# H2AR1_Backend.net
KiCad netlist of a schematic drawn in Altium Designer
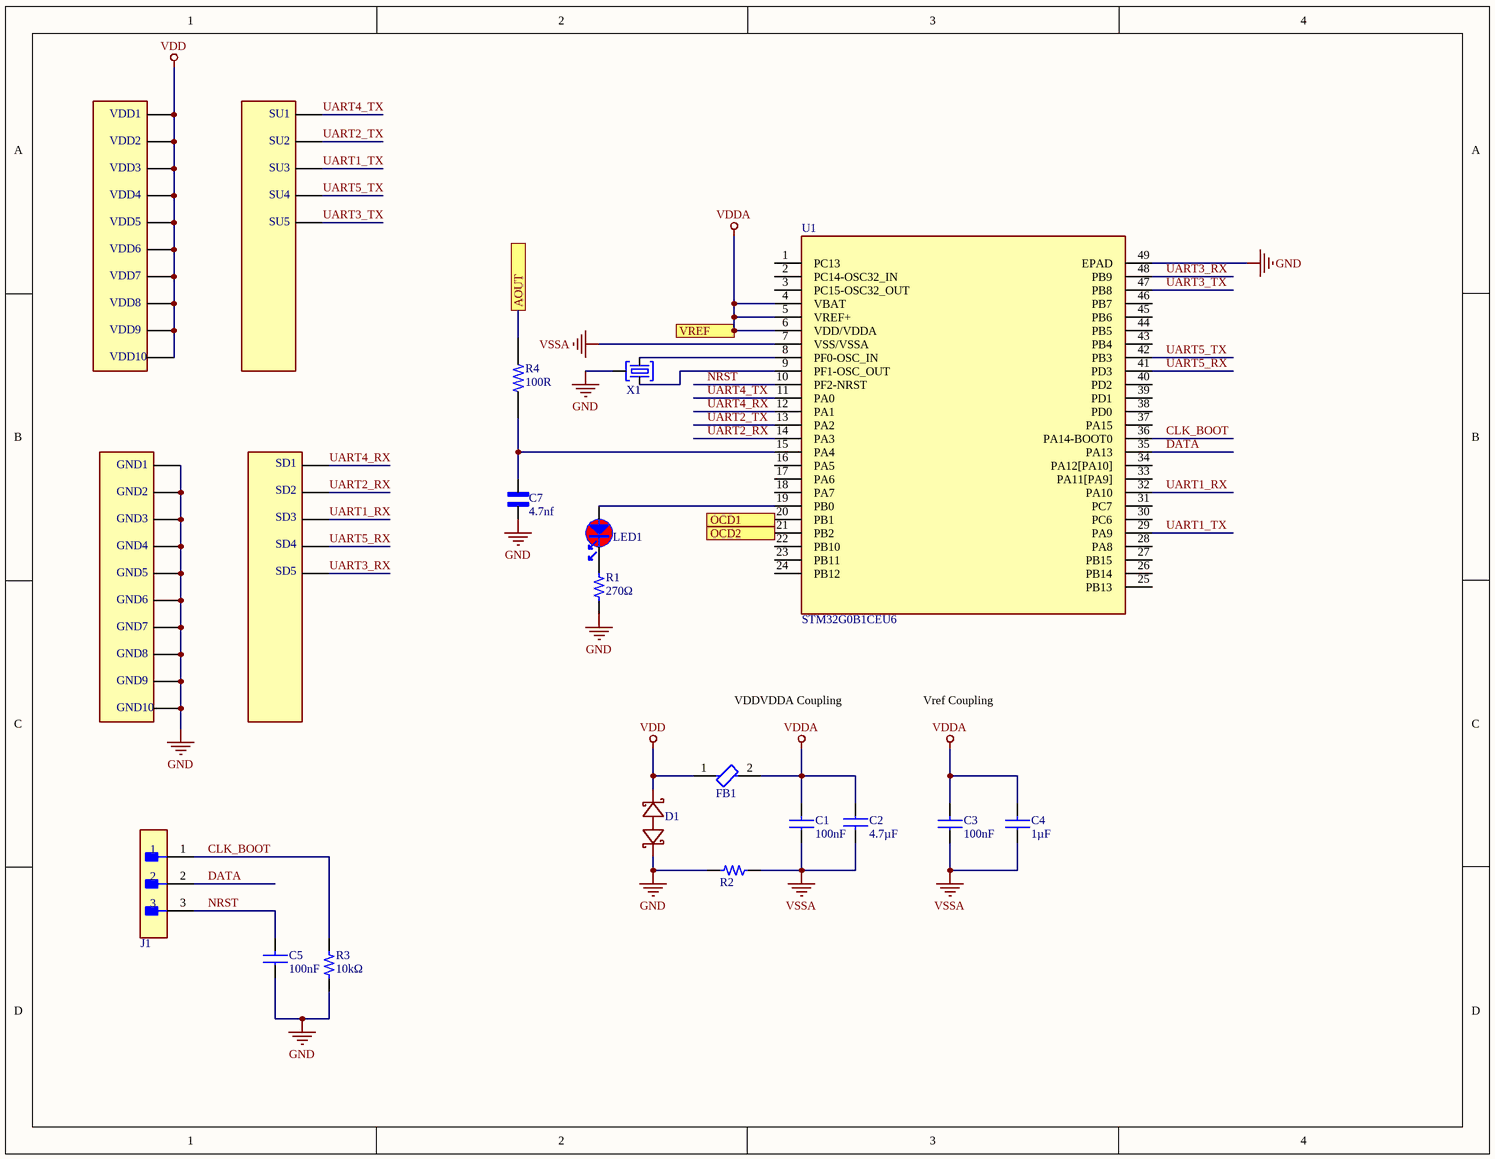
[diagram p0: H2AR1_Backend.SchDoc]

(export (version "E")
  (design (tool "Eeschema 10.0.6"))
  (components
    (comp (ref "C1")
      (value "100nF")
      (footprint "C0603")
      (fields
        (field (name "MANUFACTURER") "Samsung Electro-Mechanics")
        (field (name "MANUFACTURER PART NUMBER") "CL10B104KA8NNNC")
        (field (name "TOLERANCE") "10%")
      )
      (libsource (lib "Hexabitz Altium Library") (part "generic Capacitor"))
    )
    (comp (ref "C2")
      (value "4.7µF")
      (footprint "C0805")
      (fields
        (field (name "MANUFACTURER") "Samsung Electro-Mechanics")
        (field (name "MANUFACTURER PART NUMBER") "CL21X475KAQNNNE")
        (field (name "TOLERANCE") "10%")
      )
      (libsource (lib "Hexabitz Altium Library") (part "generic Capacitor"))
    )
    (comp (ref "C3")
      (value "100nF")
      (footprint "C0603")
      (fields
        (field (name "MANUFACTURER") "Samsung Electro-Mechanics")
        (field (name "MANUFACTURER PART NUMBER") "CL10B104KA8NNNC")
        (field (name "TOLERANCE") "10%")
      )
      (libsource (lib "Hexabitz Altium Library") (part "generic Capacitor"))
    )
    (comp (ref "C4")
      (value "1µF")
      (footprint "C0805")
      (description "Ceramic Capacitor, Ceramic, 16V, 10% +Tol, 10% -Tol, X7R, 15% TC, 1uF, Surface Mount, 0805")
      (fields
        (field (name "MANUFACTURER") "Yageo Group")
        (field (name "MANUFACTURER PART NUMBER") "CC0805KKX7R7BB105")
      )
      (libsource (lib "Hexabitz Altium Library") (part "generic Capacitor"))
    )
    (comp (ref "C5")
      (value "100nF")
      (footprint "C0603")
      (fields
        (field (name "MANUFACTURER") "Samsung Electro-Mechanics")
        (field (name "MANUFACTURER PART NUMBER") "CL10B104KA8NNNC")
        (field (name "TOLERANCE") "10%")
      )
      (libsource (lib "Hexabitz Altium Library") (part "generic Capacitor"))
    )
    (comp (ref "C7")
      (value "4.7nf")
      (footprint "CAPC0603X33N")
      (description "SMD Capacitor C0G(EIA) with Capacitance: 0.60pF Tol. 0.1pF. Rated Voltage: 50Vdc")
      (fields (field (name "MF") "Murata") (field (name "MP") "GRM0335C1HR60BA01D"))
      (libsource (lib "GRM0335C1HR60BA01D") (part "GRM0335C1HR60BA01D"))
    )
    (comp (ref "D1")
      (value "CDSOD323-T03SC")
      (footprint "SOD2513X114N")
      (description "A 3V, 350W, bi-directional, standard capacitance, SOD323 pkg TVS Diode ¦ Bourns CDSOD323-T03SC")
      (fields (field (name "MANUFACTURER") "Bourns"))
      (libsource (lib "Hexabitz Altium Library") (part "CDSOD323-T03SC"))
    )
    (comp (ref "FB1")
      (value "MMZ1608Y300B")
      (footprint "FP-MMZ1608-0_8-MFG")
      (description "Ferrite Beads 0603 30ohms 1500mA Signal Line AEC-Q200")
      (fields
        (field (name "MANUFACTURER") "TDK")
        (field (name "MANUFACTURER PART NUMBER") "MMZ1608Y300BTD25")
      )
      (libsource (lib "Hexabitz Altium Library") (part "MMZ1608Y300B"))
    )
    (comp (ref "GND1")
      (value "HEXABIT_UART_PORT")
      (footprint "HEXABIT_POWER_PORT_D")
      (libsource (lib "hexabitz_connectors.Library") (part "HEXABIT_POWER_PORT_D"))
    )
    (comp (ref "GND2")
      (value "HEXABIT_UART_PORT")
      (footprint "HEXABIT_POWER_PORT_D")
      (libsource (lib "hexabitz_connectors.Library") (part "HEXABIT_POWER_PORT_D"))
    )
    (comp (ref "GND3")
      (value "HEXABIT_UART_PORT")
      (footprint "HEXABIT_POWER_PORT_D_300R")
      (libsource (lib "hexabitz_connectors.Library") (part "HEXABIT_POWER_PORT_D_300R"))
    )
    (comp (ref "GND4")
      (value "HEXABIT_UART_PORT")
      (footprint "HEXABIT_POWER_PORT_D")
      (libsource (lib "hexabitz_connectors.Library") (part "HEXABIT_POWER_PORT_D"))
    )
    (comp (ref "GND5")
      (value "HEXABIT_UART_PORT")
      (footprint "HEXABIT_POWER_PORT_D")
      (libsource (lib "hexabitz_connectors.Library") (part "HEXABIT_POWER_PORT_D"))
    )
    (comp (ref "GND6")
      (value "HEXABIT_UART_PORT")
      (footprint "HEXABIT_POWER_PORT_D")
      (libsource (lib "hexabitz_connectors.Library") (part "HEXABIT_POWER_PORT_D"))
    )
    (comp (ref "GND7")
      (value "HEXABIT_UART_PORT")
      (footprint "HEXABIT_POWER_PORT_D")
      (libsource (lib "hexabitz_connectors.Library") (part "HEXABIT_POWER_PORT_D"))
    )
    (comp (ref "GND8")
      (value "HEXABIT_UART_PORT")
      (footprint "HEXABIT_POWER_PORT_D_300L")
      (libsource (lib "hexabitz_connectors.Library") (part "HEXABIT_POWER_PORT_D_300L"))
    )
    (comp (ref "GND9")
      (value "HEXABIT_UART_PORT")
      (footprint "HEXABIT_POWER_PORT_D")
      (libsource (lib "hexabitz_connectors.Library") (part "HEXABIT_POWER_PORT_D"))
    )
    (comp (ref "GND10")
      (value "HEXABIT_UART_PORT")
      (footprint "HEXABIT_POWER_PORT_D")
      (libsource (lib "hexabitz_connectors.Library") (part "HEXABIT_POWER_PORT_D"))
    )
    (comp (ref "J1")
      (value "TSW-103-14-G-S")
      (footprint "FP-TSW-103-14-G-S-MFG")
      (description "CONN HEADER VERT 3POS 2.54MM")
      (libsource (lib "Altium Content Vault") (part "cd3439d6ef35ae5d9b27ec4fdd3e828"))
    )
    (comp (ref "LED1")
      (value "VLMS1300-GS08")
      (footprint "FP-6_541-5092_01-4-MFG")
      (description "LED Uni-Color Super Red 639nm 2-Pin Chip 0603(1608Metric) T/R")
      (fields (field (name "MANUFACTURER") "Vishay Semiconductors"))
      (libsource (lib "Hexabitz Altium Library") (part "VLMS1300-GS08"))
    )
    (comp (ref "R1")
      (value "270Ω")
      (footprint "R0603")
      (description "Res Thick Film 0603 270 Ohm 5% 0.1W(1/10W) ±200ppm/C Pad SMD Automotive T/R")
      (fields
        (field (name "MANUFACTURER") "Panasonic")
        (field (name "MANUFACTURER PART NUMBER") "ERJ-3GEYJ271V")
      )
      (libsource (lib "Hexabitz Altium Library") (part "generic Resistor"))
    )
    (comp (ref "R2")
      (value "Manufacturer Part Number")
      (footprint "R0603")
      (libsource (lib "") (part "generic Resistor_1"))
    )
    (comp (ref "R3")
      (value "10kΩ")
      (footprint "R0603")
      (description "100mW Thick Film Resistors ±100ppm/℃ ±1% 10kΩ 0603 Chip Resistor - Surface Mount ROHS")
      (fields
        (field (name "MANUFACTURER") "Yageo Group")
        (field (name "MANUFACTURER PART NUMBER") "RC0603FR-0710KL")
      )
      (libsource (lib "") (part "generic Resistor_2"))
    )
    (comp (ref "R4")
      (value "100R")
      (footprint "RESC1607X60N")
      (description "100 Ohms Â±1% 0.1W, 1/10W Chip Resistor 0603 (1608 Metric) Moisture Resistant Thick Film")
      (fields (field (name "MF") "Yageo") (field (name "MP") "RC0603FR-07100RL"))
      (libsource (lib "RC0603FR-07100RL") (part "RC0603FR-07100RL"))
    )
    (comp (ref "SD1")
      (value "HEXABIT_UART_PORT")
      (footprint "HEXABIT_UART_PORT_D")
      (libsource (lib "hexabitz_connectors.Library") (part "HEXABIT_UART_PORT_D"))
    )
    (comp (ref "SD2")
      (value "HEXABIT_UART_PORT")
      (footprint "HEXABIT_UART_PORT_D")
      (libsource (lib "hexabitz_connectors.Library") (part "HEXABIT_UART_PORT_D"))
    )
    (comp (ref "SD3")
      (value "HEXABIT_UART_PORT")
      (footprint "HEXABIT_UART_PORT_D")
      (libsource (lib "hexabitz_connectors.Library") (part "HEXABIT_UART_PORT_D"))
    )
    (comp (ref "SD4")
      (value "HEXABIT_UART_PORT")
      (footprint "HEXABIT_UART_PORT_D")
      (libsource (lib "hexabitz_connectors.Library") (part "HEXABIT_UART_PORT_D"))
    )
    (comp (ref "SD5")
      (value "HEXABIT_UART_PORT")
      (footprint "HEXABIT_UART_PORT_D")
      (libsource (lib "hexabitz_connectors.Library") (part "HEXABIT_UART_PORT_D"))
    )
    (comp (ref "SU1")
      (value "HEXABIT_UART_PORT")
      (footprint "HEXABIT_UART_PORT_U")
      (libsource (lib "hexabitz_connectors.Library") (part "HEXABIT_UART_PORT_U"))
    )
    (comp (ref "SU2")
      (value "HEXABIT_UART_PORT")
      (footprint "HEXABIT_UART_PORT_U")
      (libsource (lib "hexabitz_connectors.Library") (part "HEXABIT_UART_PORT_U"))
    )
    (comp (ref "SU3")
      (value "HEXABIT_UART_PORT")
      (footprint "HEXABIT_UART_PORT_U")
      (libsource (lib "hexabitz_connectors.Library") (part "HEXABIT_UART_PORT_U"))
    )
    (comp (ref "SU4")
      (value "HEXABIT_UART_PORT")
      (footprint "HEXABIT_UART_PORT_U")
      (libsource (lib "hexabitz_connectors.Library") (part "HEXABIT_UART_PORT_U"))
    )
    (comp (ref "SU5")
      (value "HEXABIT_UART_PORT")
      (footprint "HEXABIT_UART_PORT_U")
      (libsource (lib "hexabitz_connectors.Library") (part "HEXABIT_UART_PORT_U"))
    )
    (comp (ref "U1")
      (value "STM32G0B1CEU6")
      (footprint "QFN50P700X700X65-49N-D")
      (description "MCU 32-bit ARM Cortex M0+ RISC 512KB Flash 1.8V/2.5V/3.3V 48-Pin UFQFPN EP Tray")
      (fields
        (field (name "MANUFACTURER") "STMicroelectronics")
        (field (name "MANUFACTURER PART NUMBER") "STM32G0B1CEU6")
      )
      (libsource (lib "Hexabitz Altium Library") (part "STM32G0B1CEU6"))
    )
    (comp (ref "VDD1")
      (value "HEXABIT_UART_PORT")
      (footprint "HEXABIT_POWER_PORT_U")
      (libsource (lib "hexabitz_connectors.Library") (part "HEXABIT_POWER_PORT_U"))
    )
    (comp (ref "VDD2")
      (value "HEXABIT_UART_PORT")
      (footprint "HEXABIT_POWER_PORT_U")
      (libsource (lib "hexabitz_connectors.Library") (part "HEXABIT_POWER_PORT_U"))
    )
    (comp (ref "VDD3")
      (value "HEXABIT_UART_PORT")
      (footprint "HEXABIT_POWER_PORT_U_300R")
      (libsource (lib "hexabitz_connectors.Library") (part "HEXABIT_POWER_PORT_U_300R"))
    )
    (comp (ref "VDD4")
      (value "HEXABIT_UART_PORT")
      (footprint "HEXABIT_POWER_PORT_U")
      (libsource (lib "hexabitz_connectors.Library") (part "HEXABIT_POWER_PORT_U"))
    )
    (comp (ref "VDD5")
      (value "HEXABIT_UART_PORT")
      (footprint "HEXABIT_POWER_PORT_U")
      (libsource (lib "hexabitz_connectors.Library") (part "HEXABIT_POWER_PORT_U"))
    )
    (comp (ref "VDD6")
      (value "HEXABIT_UART_PORT")
      (footprint "HEXABIT_POWER_PORT_U")
      (libsource (lib "hexabitz_connectors.Library") (part "HEXABIT_POWER_PORT_U"))
    )
    (comp (ref "VDD7")
      (value "HEXABIT_UART_PORT")
      (footprint "HEXABIT_POWER_PORT_U")
      (libsource (lib "hexabitz_connectors.Library") (part "HEXABIT_POWER_PORT_U"))
    )
    (comp (ref "VDD8")
      (value "HEXABIT_UART_PORT")
      (footprint "HEXABIT_POWER_PORT_U_300L")
      (libsource (lib "hexabitz_connectors.Library") (part "HEXABIT_POWER_PORT_U_300L"))
    )
    (comp (ref "VDD9")
      (value "HEXABIT_UART_PORT")
      (footprint "HEXABIT_POWER_PORT_U")
      (libsource (lib "hexabitz_connectors.Library") (part "HEXABIT_POWER_PORT_U"))
    )
    (comp (ref "VDD10")
      (value "HEXABIT_UART_PORT")
      (footprint "HEXABIT_POWER_PORT_U")
      (libsource (lib "hexabitz_connectors.Library") (part "HEXABIT_POWER_PORT_U"))
    )
    (comp (ref "X1")
      (value "CSTCE8M00G52Z-R0")
      (footprint "XTALL_CSTCE8M00G52")
      (description "Ceramic Resonator 8MHz ±0.5% (Tol) ±0.2% (Stability) 10pF 40Ohm 3-Pin CSMD T/R")
      (fields (field (name "MANUFACTURER") "Murata") (field (name "TOLERANCE") "0.5%"))
      (libsource (lib "Hexabitz Altium Library") (part "CSTCE8M00G52Z-R0"))
    )
  )
  (nets
    (net (code "1") (name "/AOUT") (class "Default")
      (node (ref "R4") (pin "1") (pinfunction "1_1") (pintype "passive"))
    )
    (net (code "2") (name "/CLK_BOOT") (class "Default")
      (node (ref "J1") (pin "1") (pinfunction "1_1") (pintype "passive"))
      (node (ref "R3") (pin "1") (pinfunction "1_1") (pintype "passive"))
      (node (ref "U1") (pin "36") (pinfunction "PA14-BOOT0_36") (pintype "passive"))
    )
    (net (code "3") (name "/DATA") (class "Default")
      (node (ref "J1") (pin "2") (pinfunction "2_2") (pintype "passive"))
      (node (ref "U1") (pin "35") (pinfunction "PA13_35") (pintype "passive"))
    )
    (net (code "4") (name "/NRST") (class "Default")
      (node (ref "C5") (pin "2") (pinfunction "2_2") (pintype "passive"))
      (node (ref "J1") (pin "3") (pinfunction "3_3") (pintype "passive"))
      (node (ref "U1") (pin "10") (pinfunction "PF2-NRST_10") (pintype "passive"))
    )
    (net (code "5") (name "/OCD1") (class "Default")
      (node (ref "U1") (pin "20") (pinfunction "PB1_20") (pintype "passive"))
    )
    (net (code "6") (name "/OCD2") (class "Default")
      (node (ref "U1") (pin "21") (pinfunction "PB2_21") (pintype "passive"))
    )
    (net (code "7") (name "/UART1_RX") (class "Default")
      (node (ref "SD3") (pin "UART_D") (pinfunction "UART_D_UART_D") (pintype "passive"))
      (node (ref "U1") (pin "32") (pinfunction "PA10_32") (pintype "passive"))
    )
    (net (code "8") (name "/UART1_TX") (class "Default")
      (node (ref "SU3") (pin "UART_U") (pinfunction "UART_U_UART_U") (pintype "passive"))
      (node (ref "U1") (pin "29") (pinfunction "PA9_29") (pintype "passive"))
    )
    (net (code "9") (name "/UART2_RX") (class "Default")
      (node (ref "SD2") (pin "UART_D") (pinfunction "UART_D_UART_D") (pintype "passive"))
      (node (ref "U1") (pin "14") (pinfunction "PA3_14") (pintype "passive"))
    )
    (net (code "10") (name "/UART2_TX") (class "Default")
      (node (ref "SU2") (pin "UART_U") (pinfunction "UART_U_UART_U") (pintype "passive"))
      (node (ref "U1") (pin "13") (pinfunction "PA2_13") (pintype "passive"))
    )
    (net (code "11") (name "/UART3_RX") (class "Default")
      (node (ref "SD5") (pin "UART_D") (pinfunction "UART_D_UART_D") (pintype "passive"))
      (node (ref "U1") (pin "48") (pinfunction "PB9_48") (pintype "passive"))
    )
    (net (code "12") (name "/UART3_TX") (class "Default")
      (node (ref "SU5") (pin "UART_U") (pinfunction "UART_U_UART_U") (pintype "passive"))
      (node (ref "U1") (pin "47") (pinfunction "PB8_47") (pintype "passive"))
    )
    (net (code "13") (name "/UART4_RX") (class "Default")
      (node (ref "SD1") (pin "UART_D") (pinfunction "UART_D_UART_D") (pintype "passive"))
      (node (ref "U1") (pin "12") (pinfunction "PA1_12") (pintype "passive"))
    )
    (net (code "14") (name "/UART4_TX") (class "Default")
      (node (ref "SU1") (pin "UART_U") (pinfunction "UART_U_UART_U") (pintype "passive"))
      (node (ref "U1") (pin "11") (pinfunction "PA0_11") (pintype "passive"))
    )
    (net (code "15") (name "/UART5_RX") (class "Default")
      (node (ref "SD4") (pin "UART_D") (pinfunction "UART_D_UART_D") (pintype "passive"))
      (node (ref "U1") (pin "41") (pinfunction "PD3_41") (pintype "passive"))
    )
    (net (code "16") (name "/UART5_TX") (class "Default")
      (node (ref "SU4") (pin "UART_U") (pinfunction "UART_U_UART_U") (pintype "passive"))
      (node (ref "U1") (pin "42") (pinfunction "PB3_42") (pintype "passive"))
    )
    (net (code "17") (name "GND") (class "Default")
      (node (ref "C5") (pin "1") (pinfunction "1_1") (pintype "passive"))
      (node (ref "C7") (pin "1") (pinfunction "1_1") (pintype "passive"))
      (node (ref "D1") (pin "1") (pinfunction "A_1") (pintype "passive"))
      (node (ref "GND1") (pin "Pwr_D") (pinfunction "Pwr_D_Pwr_D") (pintype "passive"))
      (node (ref "GND10") (pin "Pwr_D") (pinfunction "Pwr_D_Pwr_D") (pintype "passive"))
      (node (ref "GND2") (pin "Pwr_D") (pinfunction "Pwr_D_Pwr_D") (pintype "passive"))
      (node (ref "GND3") (pin "Pwr_D") (pinfunction "Pwr_D_Pwr_D") (pintype "passive"))
      (node (ref "GND4") (pin "Pwr_D") (pinfunction "Pwr_D_Pwr_D") (pintype "passive"))
      (node (ref "GND5") (pin "Pwr_D") (pinfunction "Pwr_D_Pwr_D") (pintype "passive"))
      (node (ref "GND6") (pin "Pwr_D") (pinfunction "Pwr_D_Pwr_D") (pintype "passive"))
      (node (ref "GND7") (pin "Pwr_D") (pinfunction "Pwr_D_Pwr_D") (pintype "passive"))
      (node (ref "GND8") (pin "Pwr_D") (pinfunction "Pwr_D_Pwr_D") (pintype "passive"))
      (node (ref "GND9") (pin "Pwr_D") (pinfunction "Pwr_D_Pwr_D") (pintype "passive"))
      (node (ref "R1") (pin "1") (pinfunction "1_1") (pintype "passive"))
      (node (ref "R2") (pin "1") (pinfunction "1_1") (pintype "passive"))
      (node (ref "R3") (pin "2") (pinfunction "2_2") (pintype "passive"))
      (node (ref "U1") (pin "49") (pinfunction "EPAD_49") (pintype "passive"))
      (node (ref "X1") (pin "P$2") (pinfunction "2_P$2") (pintype "passive"))
    )
    (net (code "18") (name "Net-(LED1-Pad1)") (class "Default")
      (node (ref "LED1") (pin "1") (pintype "passive"))
      (node (ref "R1") (pin "2") (pinfunction "2_2") (pintype "passive"))
    )
    (net (code "19") (name "Net-(U1-PA4)") (class "Default")
      (node (ref "C7") (pin "2") (pinfunction "2_2") (pintype "passive"))
      (node (ref "R4") (pin "2") (pinfunction "2_2") (pintype "passive"))
      (node (ref "U1") (pin "15") (pinfunction "PA4_15") (pintype "passive"))
    )
    (net (code "20") (name "Net-(U1-PB0)") (class "Default")
      (node (ref "LED1") (pin "2") (pintype "passive"))
      (node (ref "U1") (pin "19") (pinfunction "PB0_19") (pintype "passive"))
    )
    (net (code "21") (name "Net-(U1-PF0-OSC_IN)") (class "Default")
      (node (ref "U1") (pin "8") (pinfunction "PF0-OSC_IN_8") (pintype "passive"))
      (node (ref "X1") (pin "P$3") (pinfunction "3_P$3") (pintype "passive"))
    )
    (net (code "22") (name "Net-(U1-PF1-OSC_OUT)") (class "Default")
      (node (ref "U1") (pin "9") (pinfunction "PF1-OSC_OUT_9") (pintype "passive"))
      (node (ref "X1") (pin "P$1") (pinfunction "1_P$1") (pintype "passive"))
    )
    (net (code "23") (name "VDD") (class "Default")
      (node (ref "D1") (pin "2") (pinfunction "C_2") (pintype "passive"))
      (node (ref "FB1") (pin "1") (pinfunction "1_1") (pintype "passive"))
      (node (ref "VDD1") (pin "Pwr_U") (pinfunction "Pwr_U_Pwr_U") (pintype "passive"))
      (node (ref "VDD10") (pin "Pwr_U") (pinfunction "Pwr_U_Pwr_U") (pintype "passive"))
      (node (ref "VDD2") (pin "Pwr_U") (pinfunction "Pwr_U_Pwr_U") (pintype "passive"))
      (node (ref "VDD3") (pin "Pwr_U") (pinfunction "Pwr_U_Pwr_U") (pintype "passive"))
      (node (ref "VDD4") (pin "Pwr_U") (pinfunction "Pwr_U_Pwr_U") (pintype "passive"))
      (node (ref "VDD5") (pin "Pwr_U") (pinfunction "Pwr_U_Pwr_U") (pintype "passive"))
      (node (ref "VDD6") (pin "Pwr_U") (pinfunction "Pwr_U_Pwr_U") (pintype "passive"))
      (node (ref "VDD7") (pin "Pwr_U") (pinfunction "Pwr_U_Pwr_U") (pintype "passive"))
      (node (ref "VDD8") (pin "Pwr_U") (pinfunction "Pwr_U_Pwr_U") (pintype "passive"))
      (node (ref "VDD9") (pin "Pwr_U") (pinfunction "Pwr_U_Pwr_U") (pintype "passive"))
    )
    (net (code "24") (name "VDDA") (class "Default")
      (node (ref "C1") (pin "2") (pinfunction "2_2") (pintype "passive"))
      (node (ref "C2") (pin "1") (pinfunction "1_1") (pintype "passive"))
      (node (ref "C3") (pin "2") (pinfunction "2_2") (pintype "passive"))
      (node (ref "C4") (pin "2") (pinfunction "2_2") (pintype "passive"))
      (node (ref "FB1") (pin "2") (pinfunction "2_2") (pintype "passive"))
      (node (ref "U1") (pin "4") (pinfunction "VBAT_4") (pintype "passive"))
      (node (ref "U1") (pin "5") (pinfunction "VREF+_5") (pintype "passive"))
      (node (ref "U1") (pin "6") (pinfunction "VDD/VDDA_6") (pintype "passive"))
    )
    (net (code "25") (name "VSSA") (class "Default")
      (node (ref "C1") (pin "1") (pinfunction "1_1") (pintype "passive"))
      (node (ref "C2") (pin "2") (pinfunction "2_2") (pintype "passive"))
      (node (ref "C3") (pin "1") (pinfunction "1_1") (pintype "passive"))
      (node (ref "C4") (pin "1") (pinfunction "1_1") (pintype "passive"))
      (node (ref "R2") (pin "2") (pinfunction "2_2") (pintype "passive"))
      (node (ref "U1") (pin "7") (pinfunction "VSS/VSSA_7") (pintype "passive"))
    )
    (net (code "26") (name "unconnected-(U1-PA5-Pad16)") (class "Default")
      (node (ref "U1") (pin "16") (pinfunction "PA5_16") (pintype "passive"))
    )
    (net (code "27") (name "unconnected-(U1-PA6-Pad17)") (class "Default")
      (node (ref "U1") (pin "17") (pinfunction "PA6_17") (pintype "passive"))
    )
    (net (code "28") (name "unconnected-(U1-PA7-Pad18)") (class "Default")
      (node (ref "U1") (pin "18") (pinfunction "PA7_18") (pintype "passive"))
    )
    (net (code "29") (name "unconnected-(U1-PA8-Pad28)") (class "Default")
      (node (ref "U1") (pin "28") (pinfunction "PA8_28") (pintype "passive"))
    )
    (net (code "30") (name "unconnected-(U1-PA11[PA9]-Pad33)") (class "Default")
      (node (ref "U1") (pin "33") (pinfunction "PA11[PA9]_33") (pintype "passive"))
    )
    (net (code "31") (name "unconnected-(U1-PA12[PA10]-Pad34)") (class "Default")
      (node (ref "U1") (pin "34") (pinfunction "PA12[PA10]_34") (pintype "passive"))
    )
    (net (code "32") (name "unconnected-(U1-PA15-Pad37)") (class "Default")
      (node (ref "U1") (pin "37") (pinfunction "PA15_37") (pintype "passive"))
    )
    (net (code "33") (name "unconnected-(U1-PB4-Pad43)") (class "Default")
      (node (ref "U1") (pin "43") (pinfunction "PB4_43") (pintype "passive"))
    )
    (net (code "34") (name "unconnected-(U1-PB5-Pad44)") (class "Default")
      (node (ref "U1") (pin "44") (pinfunction "PB5_44") (pintype "passive"))
    )
    (net (code "35") (name "unconnected-(U1-PB6-Pad45)") (class "Default")
      (node (ref "U1") (pin "45") (pinfunction "PB6_45") (pintype "passive"))
    )
    (net (code "36") (name "unconnected-(U1-PB7-Pad46)") (class "Default")
      (node (ref "U1") (pin "46") (pinfunction "PB7_46") (pintype "passive"))
    )
    (net (code "37") (name "unconnected-(U1-PB10-Pad22)") (class "Default")
      (node (ref "U1") (pin "22") (pinfunction "PB10_22") (pintype "passive"))
    )
    (net (code "38") (name "unconnected-(U1-PB11-Pad23)") (class "Default")
      (node (ref "U1") (pin "23") (pinfunction "PB11_23") (pintype "passive"))
    )
    (net (code "39") (name "unconnected-(U1-PB12-Pad24)") (class "Default")
      (node (ref "U1") (pin "24") (pinfunction "PB12_24") (pintype "passive"))
    )
    (net (code "40") (name "unconnected-(U1-PB13-Pad25)") (class "Default")
      (node (ref "U1") (pin "25") (pinfunction "PB13_25") (pintype "passive"))
    )
    (net (code "41") (name "unconnected-(U1-PB14-Pad26)") (class "Default")
      (node (ref "U1") (pin "26") (pinfunction "PB14_26") (pintype "passive"))
    )
    (net (code "42") (name "unconnected-(U1-PB15-Pad27)") (class "Default")
      (node (ref "U1") (pin "27") (pinfunction "PB15_27") (pintype "passive"))
    )
    (net (code "43") (name "unconnected-(U1-PC6-Pad30)") (class "Default")
      (node (ref "U1") (pin "30") (pinfunction "PC6_30") (pintype "passive"))
    )
    (net (code "44") (name "unconnected-(U1-PC7-Pad31)") (class "Default")
      (node (ref "U1") (pin "31") (pinfunction "PC7_31") (pintype "passive"))
    )
    (net (code "45") (name "unconnected-(U1-PC13-Pad1)") (class "Default")
      (node (ref "U1") (pin "1") (pinfunction "PC13_1") (pintype "passive"))
    )
    (net (code "46") (name "unconnected-(U1-PC14-OSC32_IN-Pad2)") (class "Default")
      (node (ref "U1") (pin "2") (pinfunction "PC14-OSC32_IN_2") (pintype "passive"))
    )
    (net (code "47") (name "unconnected-(U1-PC15-OSC32_OUT-Pad3)") (class "Default")
      (node (ref "U1") (pin "3") (pinfunction "PC15-OSC32_OUT_3") (pintype "passive"))
    )
    (net (code "48") (name "unconnected-(U1-PD0-Pad38)") (class "Default")
      (node (ref "U1") (pin "38") (pinfunction "PD0_38") (pintype "passive"))
    )
    (net (code "49") (name "unconnected-(U1-PD1-Pad39)") (class "Default")
      (node (ref "U1") (pin "39") (pinfunction "PD1_39") (pintype "passive"))
    )
    (net (code "50") (name "unconnected-(U1-PD2-Pad40)") (class "Default")
      (node (ref "U1") (pin "40") (pinfunction "PD2_40") (pintype "passive"))
    )
  )
)
